# AMC_Connector.net
KiCad netlist of a schematic drawn in Altium Designer
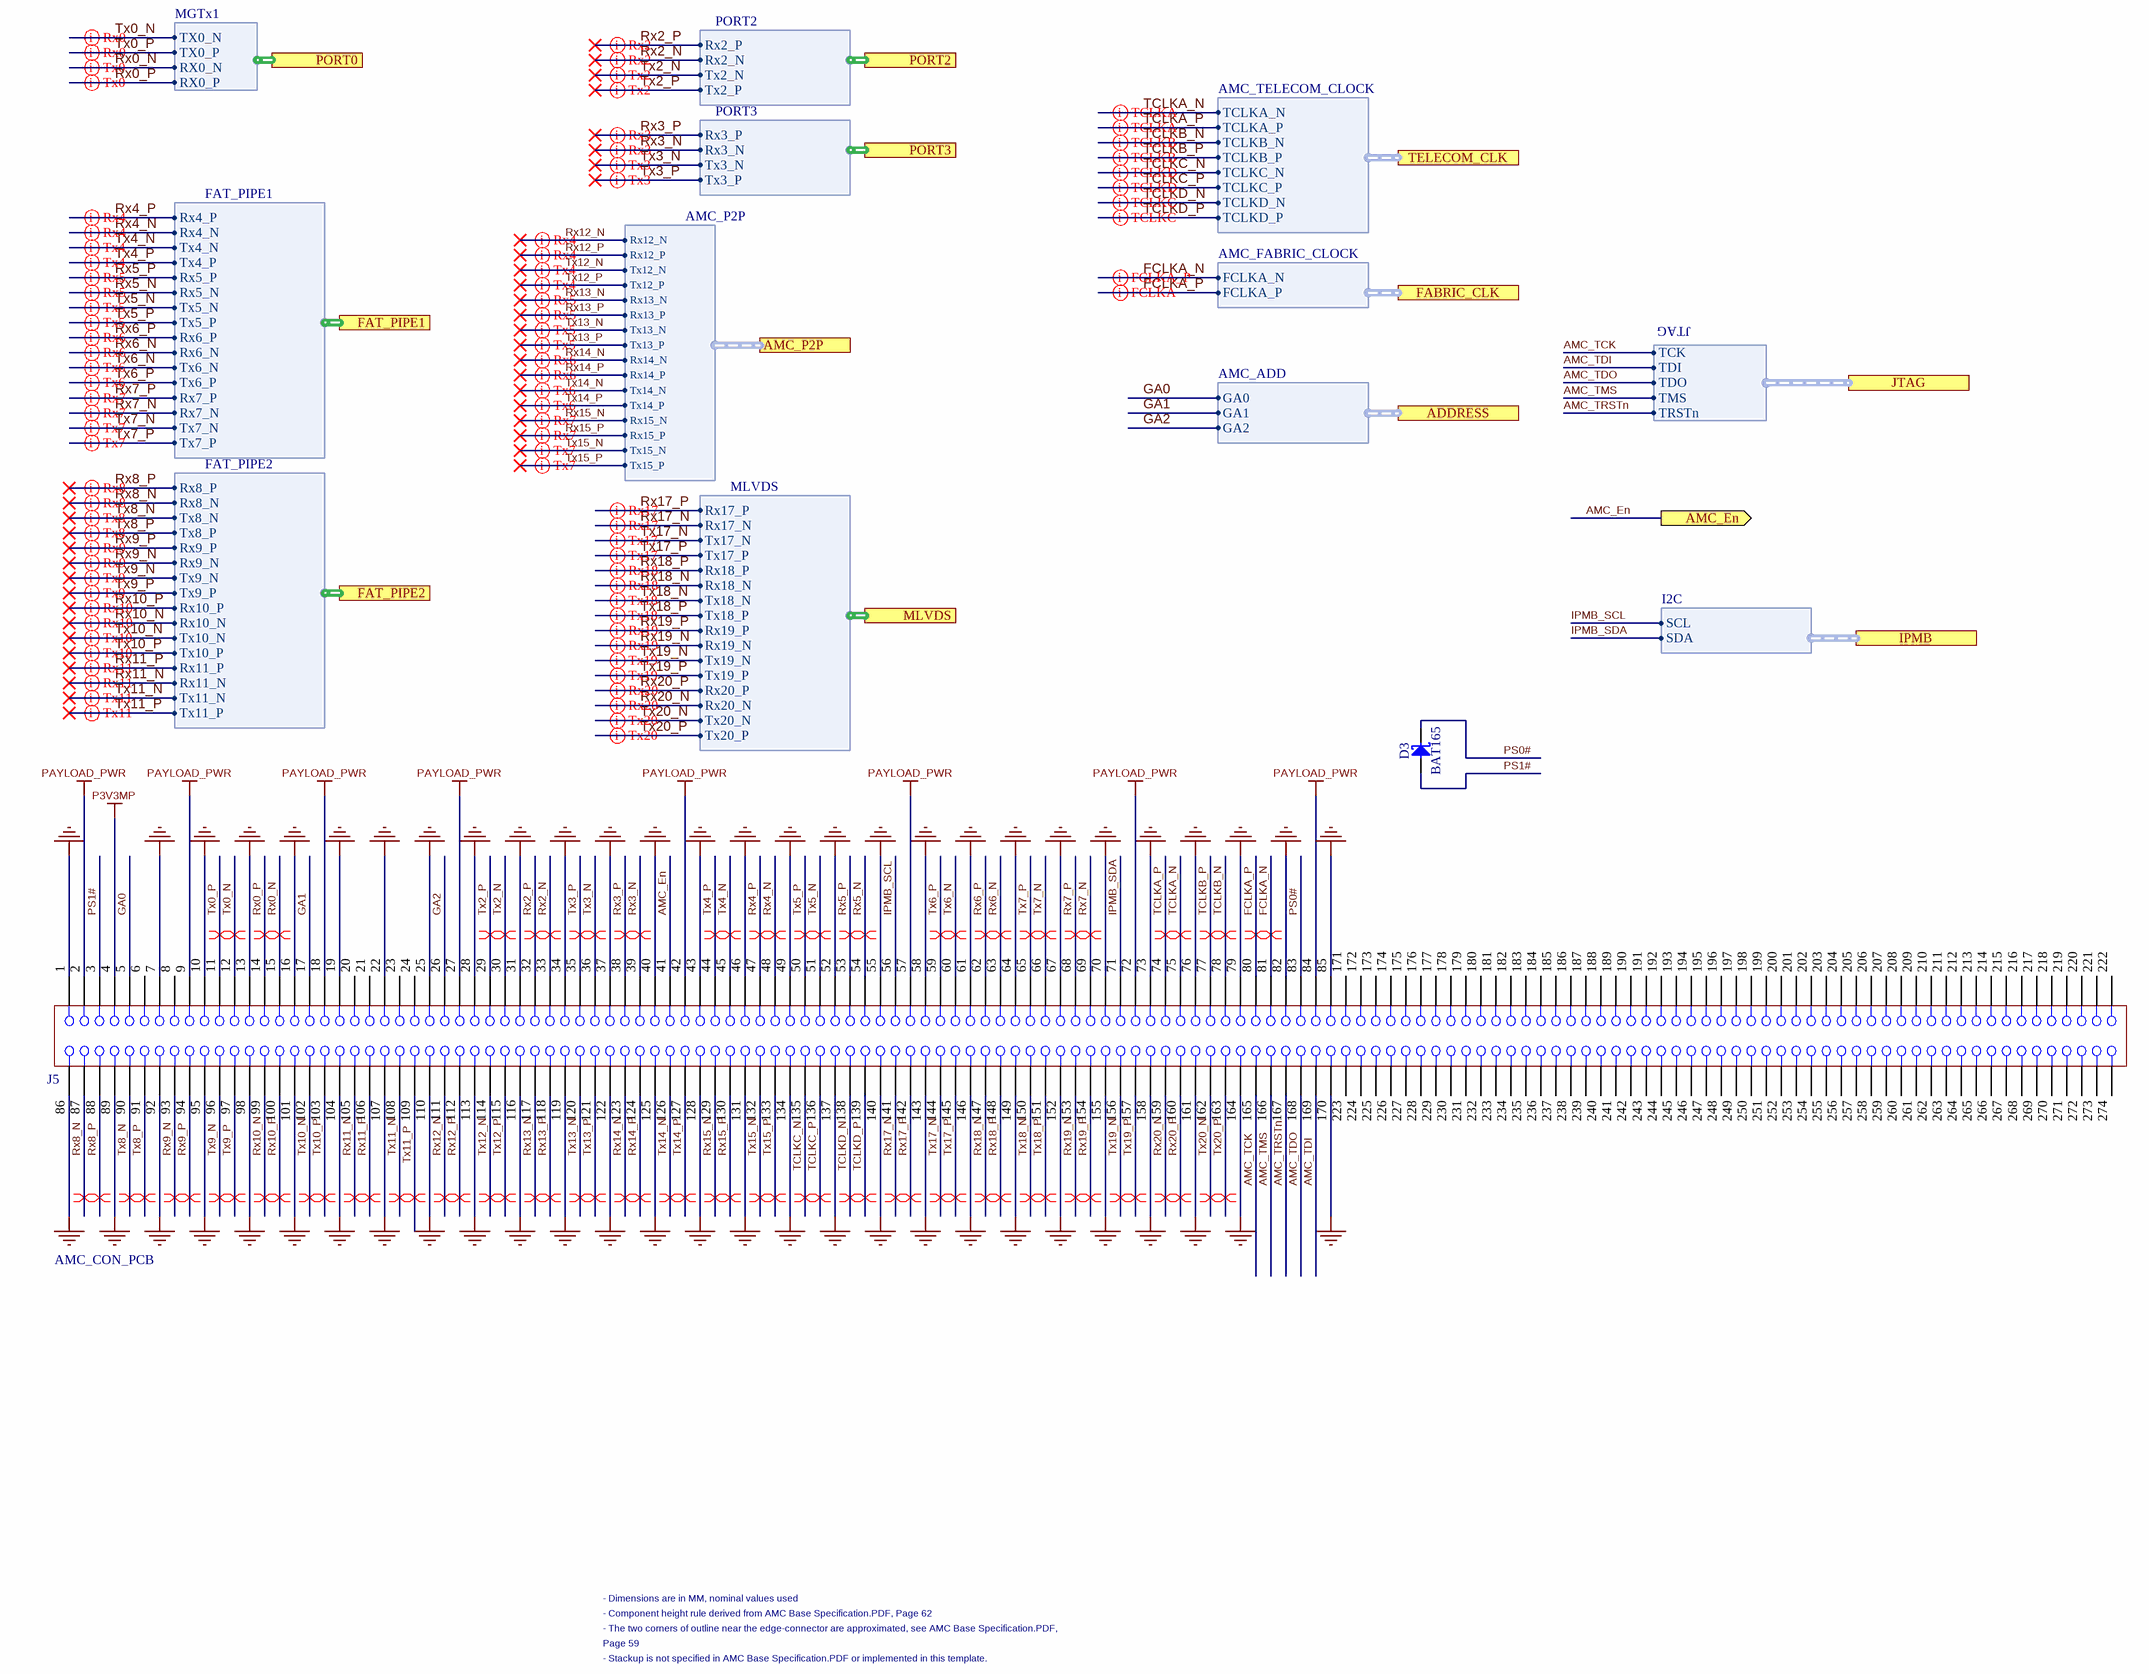
[diagram p0: AMC_Connector.SchDoc]

(export (version "E")
  (design (tool "Eeschema 10.0.6"))
  (components
    (comp (ref "D3")
      (value "BAT165")
      (footprint "SOD2512X110N")
      (description "Schottky Diode")
      (fields
        (field (name "MANUFACTURER") "INFINEON")
        (field (name "VOLTAGE") "40V")
        (field (name "AUTHOR") "CERN DEM JLC")
      )
      (libsource (lib "ICs And Semiconductors") (part "Diode Schottky"))
    )
    (comp (ref "J5")
      (value "AMC_CON_PCB")
      (fields (field (name "MANUFACTURER PART NUMBER") "pcb"))
      (libsource (lib "altium-import") (part "root_0__*"))
    )
  )
  (nets
    (net (code "13") (name "/AMC_En") (class "Default")
      (node (ref "J5") (pin "41") (pinfunction "41_41") (pintype "passive"))
    )
    (net (code "14") (name "/AMC_TCK") (class "Default")
      (node (ref "J5") (pin "165") (pinfunction "165_165") (pintype "passive"))
    )
    (net (code "15") (name "/AMC_TDI") (class "Default")
      (node (ref "J5") (pin "169") (pinfunction "169_169") (pintype "passive"))
    )
    (net (code "16") (name "/AMC_TDO") (class "Default")
      (node (ref "J5") (pin "168") (pinfunction "168_168") (pintype "passive"))
    )
    (net (code "17") (name "/AMC_TMS") (class "Default")
      (node (ref "J5") (pin "166") (pinfunction "166_166") (pintype "passive"))
    )
    (net (code "18") (name "/AMC_TRSTn") (class "Default")
      (node (ref "J5") (pin "167") (pinfunction "167_167") (pintype "passive"))
    )
    (net (code "19") (name "/FCLKA_N") (class "Default")
      (node (ref "J5") (pin "81") (pinfunction "81_81") (pintype "passive"))
    )
    (net (code "20") (name "/FCLKA_P") (class "Default")
      (node (ref "J5") (pin "80") (pinfunction "80_80") (pintype "passive"))
    )
    (net (code "21") (name "/GA0") (class "Default")
      (node (ref "J5") (pin "5") (pinfunction "5_5") (pintype "passive"))
    )
    (net (code "22") (name "/GA1") (class "Default")
      (node (ref "J5") (pin "17") (pinfunction "17_17") (pintype "passive"))
    )
    (net (code "23") (name "/GA2") (class "Default")
      (node (ref "J5") (pin "26") (pinfunction "26_26") (pintype "passive"))
    )
    (net (code "24") (name "/IPMB_SCL") (class "Default")
      (node (ref "J5") (pin "56") (pinfunction "56_56") (pintype "passive"))
    )
    (net (code "25") (name "/IPMB_SDA") (class "Default")
      (node (ref "J5") (pin "71") (pinfunction "71_71") (pintype "passive"))
    )
    (net (code "26") (name "/PS0#") (class "Default")
      (node (ref "D3") (pin "1") (pinfunction "C_1") (pintype "passive"))
      (node (ref "J5") (pin "83") (pinfunction "83_83") (pintype "passive"))
    )
    (net (code "27") (name "/PS1#") (class "Default")
      (node (ref "D3") (pin "2") (pinfunction "A_2") (pintype "passive"))
      (node (ref "J5") (pin "3") (pinfunction "3_3") (pintype "passive"))
    )
    (net (code "28") (name "/Rx0_N") (class "Default")
      (node (ref "J5") (pin "15") (pinfunction "15_15") (pintype "passive"))
    )
    (net (code "29") (name "/Rx0_P") (class "Default")
      (node (ref "J5") (pin "14") (pinfunction "14_14") (pintype "passive"))
    )
    (net (code "30") (name "/Rx2_N") (class "Default")
      (node (ref "J5") (pin "33") (pinfunction "33_33") (pintype "passive"))
    )
    (net (code "31") (name "/Rx2_P") (class "Default")
      (node (ref "J5") (pin "32") (pinfunction "32_32") (pintype "passive"))
    )
    (net (code "32") (name "/Rx3_N") (class "Default")
      (node (ref "J5") (pin "39") (pinfunction "39_39") (pintype "passive"))
    )
    (net (code "33") (name "/Rx3_P") (class "Default")
      (node (ref "J5") (pin "38") (pinfunction "38_38") (pintype "passive"))
    )
    (net (code "34") (name "/Rx4_N") (class "Default")
      (node (ref "J5") (pin "48") (pinfunction "48_48") (pintype "passive"))
    )
    (net (code "35") (name "/Rx4_P") (class "Default")
      (node (ref "J5") (pin "47") (pinfunction "47_47") (pintype "passive"))
    )
    (net (code "36") (name "/Rx5_N") (class "Default")
      (node (ref "J5") (pin "54") (pinfunction "54_54") (pintype "passive"))
    )
    (net (code "37") (name "/Rx5_P") (class "Default")
      (node (ref "J5") (pin "53") (pinfunction "53_53") (pintype "passive"))
    )
    (net (code "38") (name "/Rx6_N") (class "Default")
      (node (ref "J5") (pin "63") (pinfunction "63_63") (pintype "passive"))
    )
    (net (code "39") (name "/Rx6_P") (class "Default")
      (node (ref "J5") (pin "62") (pinfunction "62_62") (pintype "passive"))
    )
    (net (code "40") (name "/Rx7_N") (class "Default")
      (node (ref "J5") (pin "69") (pinfunction "69_69") (pintype "passive"))
    )
    (net (code "41") (name "/Rx7_P") (class "Default")
      (node (ref "J5") (pin "68") (pinfunction "68_68") (pintype "passive"))
    )
    (net (code "42") (name "/Rx8_N") (class "Default")
      (node (ref "J5") (pin "87") (pinfunction "87_87") (pintype "passive"))
    )
    (net (code "43") (name "/Rx8_P") (class "Default")
      (node (ref "J5") (pin "88") (pinfunction "88_88") (pintype "passive"))
    )
    (net (code "44") (name "/Rx9_N") (class "Default")
      (node (ref "J5") (pin "93") (pinfunction "93_93") (pintype "passive"))
    )
    (net (code "45") (name "/Rx9_P") (class "Default")
      (node (ref "J5") (pin "94") (pinfunction "94_94") (pintype "passive"))
    )
    (net (code "46") (name "/Rx10_N") (class "Default")
      (node (ref "J5") (pin "99") (pinfunction "99_99") (pintype "passive"))
    )
    (net (code "47") (name "/Rx10_P") (class "Default")
      (node (ref "J5") (pin "100") (pinfunction "100_100") (pintype "passive"))
    )
    (net (code "48") (name "/Rx11_N") (class "Default")
      (node (ref "J5") (pin "105") (pinfunction "105_105") (pintype "passive"))
    )
    (net (code "49") (name "/Rx11_P") (class "Default")
      (node (ref "J5") (pin "106") (pinfunction "106_106") (pintype "passive"))
    )
    (net (code "50") (name "/Rx12_N") (class "Default")
      (node (ref "J5") (pin "111") (pinfunction "111_111") (pintype "passive"))
    )
    (net (code "51") (name "/Rx12_P") (class "Default")
      (node (ref "J5") (pin "112") (pinfunction "112_112") (pintype "passive"))
    )
    (net (code "52") (name "/Rx13_N") (class "Default")
      (node (ref "J5") (pin "117") (pinfunction "117_117") (pintype "passive"))
    )
    (net (code "53") (name "/Rx13_P") (class "Default")
      (node (ref "J5") (pin "118") (pinfunction "118_118") (pintype "passive"))
    )
    (net (code "54") (name "/Rx14_N") (class "Default")
      (node (ref "J5") (pin "123") (pinfunction "123_123") (pintype "passive"))
    )
    (net (code "55") (name "/Rx14_P") (class "Default")
      (node (ref "J5") (pin "124") (pinfunction "124_124") (pintype "passive"))
    )
    (net (code "56") (name "/Rx15_N") (class "Default")
      (node (ref "J5") (pin "129") (pinfunction "129_129") (pintype "passive"))
    )
    (net (code "57") (name "/Rx15_P") (class "Default")
      (node (ref "J5") (pin "130") (pinfunction "130_130") (pintype "passive"))
    )
    (net (code "58") (name "/Rx17_N") (class "Default")
      (node (ref "J5") (pin "141") (pinfunction "141_141") (pintype "passive"))
    )
    (net (code "59") (name "/Rx17_P") (class "Default")
      (node (ref "J5") (pin "142") (pinfunction "142_142") (pintype "passive"))
    )
    (net (code "60") (name "/Rx18_N") (class "Default")
      (node (ref "J5") (pin "147") (pinfunction "147_147") (pintype "passive"))
    )
    (net (code "61") (name "/Rx18_P") (class "Default")
      (node (ref "J5") (pin "148") (pinfunction "148_148") (pintype "passive"))
    )
    (net (code "62") (name "/Rx19_N") (class "Default")
      (node (ref "J5") (pin "153") (pinfunction "153_153") (pintype "passive"))
    )
    (net (code "63") (name "/Rx19_P") (class "Default")
      (node (ref "J5") (pin "154") (pinfunction "154_154") (pintype "passive"))
    )
    (net (code "64") (name "/Rx20_N") (class "Default")
      (node (ref "J5") (pin "159") (pinfunction "159_159") (pintype "passive"))
    )
    (net (code "65") (name "/Rx20_P") (class "Default")
      (node (ref "J5") (pin "160") (pinfunction "160_160") (pintype "passive"))
    )
    (net (code "66") (name "/TCLKA_N") (class "Default")
      (node (ref "J5") (pin "75") (pinfunction "75_75") (pintype "passive"))
    )
    (net (code "67") (name "/TCLKA_P") (class "Default")
      (node (ref "J5") (pin "74") (pinfunction "74_74") (pintype "passive"))
    )
    (net (code "68") (name "/TCLKB_N") (class "Default")
      (node (ref "J5") (pin "78") (pinfunction "78_78") (pintype "passive"))
    )
    (net (code "69") (name "/TCLKB_P") (class "Default")
      (node (ref "J5") (pin "77") (pinfunction "77_77") (pintype "passive"))
    )
    (net (code "70") (name "/TCLKC_N") (class "Default")
      (node (ref "J5") (pin "135") (pinfunction "135_135") (pintype "passive"))
    )
    (net (code "71") (name "/TCLKC_P") (class "Default")
      (node (ref "J5") (pin "136") (pinfunction "136_136") (pintype "passive"))
    )
    (net (code "72") (name "/TCLKD_N") (class "Default")
      (node (ref "J5") (pin "138") (pinfunction "138_138") (pintype "passive"))
    )
    (net (code "73") (name "/TCLKD_P") (class "Default")
      (node (ref "J5") (pin "139") (pinfunction "139_139") (pintype "passive"))
    )
    (net (code "74") (name "/Tx0_N") (class "Default")
      (node (ref "J5") (pin "12") (pinfunction "12_12") (pintype "passive"))
    )
    (net (code "75") (name "/Tx0_P") (class "Default")
      (node (ref "J5") (pin "11") (pinfunction "11_11") (pintype "passive"))
    )
    (net (code "76") (name "/Tx2_N") (class "Default")
      (node (ref "J5") (pin "30") (pinfunction "30_30") (pintype "passive"))
    )
    (net (code "77") (name "/Tx2_P") (class "Default")
      (node (ref "J5") (pin "29") (pinfunction "29_29") (pintype "passive"))
    )
    (net (code "78") (name "/Tx3_N") (class "Default")
      (node (ref "J5") (pin "36") (pinfunction "36_36") (pintype "passive"))
    )
    (net (code "79") (name "/Tx3_P") (class "Default")
      (node (ref "J5") (pin "35") (pinfunction "35_35") (pintype "passive"))
    )
    (net (code "80") (name "/Tx4_N") (class "Default")
      (node (ref "J5") (pin "45") (pinfunction "45_45") (pintype "passive"))
    )
    (net (code "81") (name "/Tx4_P") (class "Default")
      (node (ref "J5") (pin "44") (pinfunction "44_44") (pintype "passive"))
    )
    (net (code "82") (name "/Tx5_N") (class "Default")
      (node (ref "J5") (pin "51") (pinfunction "51_51") (pintype "passive"))
    )
    (net (code "83") (name "/Tx5_P") (class "Default")
      (node (ref "J5") (pin "50") (pinfunction "50_50") (pintype "passive"))
    )
    (net (code "84") (name "/Tx6_N") (class "Default")
      (node (ref "J5") (pin "60") (pinfunction "60_60") (pintype "passive"))
    )
    (net (code "85") (name "/Tx6_P") (class "Default")
      (node (ref "J5") (pin "59") (pinfunction "59_59") (pintype "passive"))
    )
    (net (code "86") (name "/Tx7_N") (class "Default")
      (node (ref "J5") (pin "66") (pinfunction "66_66") (pintype "passive"))
    )
    (net (code "87") (name "/Tx7_P") (class "Default")
      (node (ref "J5") (pin "65") (pinfunction "65_65") (pintype "passive"))
    )
    (net (code "88") (name "/Tx8_N") (class "Default")
      (node (ref "J5") (pin "90") (pinfunction "90_90") (pintype "passive"))
    )
    (net (code "89") (name "/Tx8_P") (class "Default")
      (node (ref "J5") (pin "91") (pinfunction "91_91") (pintype "passive"))
    )
    (net (code "90") (name "/Tx9_N") (class "Default")
      (node (ref "J5") (pin "96") (pinfunction "96_96") (pintype "passive"))
    )
    (net (code "91") (name "/Tx9_P") (class "Default")
      (node (ref "J5") (pin "97") (pinfunction "97_97") (pintype "passive"))
    )
    (net (code "92") (name "/Tx10_N") (class "Default")
      (node (ref "J5") (pin "102") (pinfunction "102_102") (pintype "passive"))
    )
    (net (code "93") (name "/Tx10_P") (class "Default")
      (node (ref "J5") (pin "103") (pinfunction "103_103") (pintype "passive"))
    )
    (net (code "94") (name "/Tx11_N") (class "Default")
      (node (ref "J5") (pin "108") (pinfunction "108_108") (pintype "passive"))
    )
    (net (code "95") (name "/Tx11_P") (class "Default")
      (node (ref "J5") (pin "109") (pinfunction "109_109") (pintype "passive"))
    )
    (net (code "96") (name "/Tx12_N") (class "Default")
      (node (ref "J5") (pin "114") (pinfunction "114_114") (pintype "passive"))
    )
    (net (code "97") (name "/Tx12_P") (class "Default")
      (node (ref "J5") (pin "115") (pinfunction "115_115") (pintype "passive"))
    )
    (net (code "98") (name "/Tx13_N") (class "Default")
      (node (ref "J5") (pin "120") (pinfunction "120_120") (pintype "passive"))
    )
    (net (code "99") (name "/Tx13_P") (class "Default")
      (node (ref "J5") (pin "121") (pinfunction "121_121") (pintype "passive"))
    )
    (net (code "100") (name "/Tx14_N") (class "Default")
      (node (ref "J5") (pin "126") (pinfunction "126_126") (pintype "passive"))
    )
    (net (code "101") (name "/Tx14_P") (class "Default")
      (node (ref "J5") (pin "127") (pinfunction "127_127") (pintype "passive"))
    )
    (net (code "102") (name "/Tx15_N") (class "Default")
      (node (ref "J5") (pin "132") (pinfunction "132_132") (pintype "passive"))
    )
    (net (code "103") (name "/Tx15_P") (class "Default")
      (node (ref "J5") (pin "133") (pinfunction "133_133") (pintype "passive"))
    )
    (net (code "104") (name "/Tx17_N") (class "Default")
      (node (ref "J5") (pin "144") (pinfunction "144_144") (pintype "passive"))
    )
    (net (code "105") (name "/Tx17_P") (class "Default")
      (node (ref "J5") (pin "145") (pinfunction "145_145") (pintype "passive"))
    )
    (net (code "106") (name "/Tx18_N") (class "Default")
      (node (ref "J5") (pin "150") (pinfunction "150_150") (pintype "passive"))
    )
    (net (code "107") (name "/Tx18_P") (class "Default")
      (node (ref "J5") (pin "151") (pinfunction "151_151") (pintype "passive"))
    )
    (net (code "108") (name "/Tx19_N") (class "Default")
      (node (ref "J5") (pin "156") (pinfunction "156_156") (pintype "passive"))
    )
    (net (code "109") (name "/Tx19_P") (class "Default")
      (node (ref "J5") (pin "157") (pinfunction "157_157") (pintype "passive"))
    )
    (net (code "110") (name "/Tx20_N") (class "Default")
      (node (ref "J5") (pin "162") (pinfunction "162_162") (pintype "passive"))
    )
    (net (code "111") (name "/Tx20_P") (class "Default")
      (node (ref "J5") (pin "163") (pinfunction "163_163") (pintype "passive"))
    )
    (net (code "124") (name "GND") (class "Default")
      (node (ref "J5") (pin "1") (pinfunction "1_1") (pintype "passive"))
      (node (ref "J5") (pin "10") (pinfunction "10_10") (pintype "passive"))
      (node (ref "J5") (pin "101") (pinfunction "101_101") (pintype "passive"))
      (node (ref "J5") (pin "104") (pinfunction "104_104") (pintype "passive"))
      (node (ref "J5") (pin "107") (pinfunction "107_107") (pintype "passive"))
      (node (ref "J5") (pin "110") (pinfunction "110_110") (pintype "passive"))
      (node (ref "J5") (pin "113") (pinfunction "113_113") (pintype "passive"))
      (node (ref "J5") (pin "116") (pinfunction "116_116") (pintype "passive"))
      (node (ref "J5") (pin "119") (pinfunction "119_119") (pintype "passive"))
      (node (ref "J5") (pin "122") (pinfunction "122_122") (pintype "passive"))
      (node (ref "J5") (pin "125") (pinfunction "125_125") (pintype "passive"))
      (node (ref "J5") (pin "128") (pinfunction "128_128") (pintype "passive"))
      (node (ref "J5") (pin "13") (pinfunction "13_13") (pintype "passive"))
      (node (ref "J5") (pin "131") (pinfunction "131_131") (pintype "passive"))
      (node (ref "J5") (pin "134") (pinfunction "134_134") (pintype "passive"))
      (node (ref "J5") (pin "137") (pinfunction "137_137") (pintype "passive"))
      (node (ref "J5") (pin "140") (pinfunction "140_140") (pintype "passive"))
      (node (ref "J5") (pin "143") (pinfunction "143_143") (pintype "passive"))
      (node (ref "J5") (pin "146") (pinfunction "146_146") (pintype "passive"))
      (node (ref "J5") (pin "149") (pinfunction "149_149") (pintype "passive"))
      (node (ref "J5") (pin "152") (pinfunction "152_152") (pintype "passive"))
      (node (ref "J5") (pin "155") (pinfunction "155_155") (pintype "passive"))
      (node (ref "J5") (pin "158") (pinfunction "158_158") (pintype "passive"))
      (node (ref "J5") (pin "16") (pinfunction "16_16") (pintype "passive"))
      (node (ref "J5") (pin "161") (pinfunction "161_161") (pintype "passive"))
      (node (ref "J5") (pin "164") (pinfunction "164_164") (pintype "passive"))
      (node (ref "J5") (pin "170") (pinfunction "170_170") (pintype "passive"))
      (node (ref "J5") (pin "19") (pinfunction "19_19") (pintype "passive"))
      (node (ref "J5") (pin "22") (pinfunction "22_22") (pintype "passive"))
      (node (ref "J5") (pin "25") (pinfunction "25_25") (pintype "passive"))
      (node (ref "J5") (pin "28") (pinfunction "28_28") (pintype "passive"))
      (node (ref "J5") (pin "31") (pinfunction "31_31") (pintype "passive"))
      (node (ref "J5") (pin "34") (pinfunction "34_34") (pintype "passive"))
      (node (ref "J5") (pin "37") (pinfunction "37_37") (pintype "passive"))
      (node (ref "J5") (pin "40") (pinfunction "40_40") (pintype "passive"))
      (node (ref "J5") (pin "43") (pinfunction "43_43") (pintype "passive"))
      (node (ref "J5") (pin "46") (pinfunction "46_46") (pintype "passive"))
      (node (ref "J5") (pin "49") (pinfunction "49_49") (pintype "passive"))
      (node (ref "J5") (pin "52") (pinfunction "52_52") (pintype "passive"))
      (node (ref "J5") (pin "55") (pinfunction "55_55") (pintype "passive"))
      (node (ref "J5") (pin "58") (pinfunction "58_58") (pintype "passive"))
      (node (ref "J5") (pin "61") (pinfunction "61_61") (pintype "passive"))
      (node (ref "J5") (pin "64") (pinfunction "64_64") (pintype "passive"))
      (node (ref "J5") (pin "67") (pinfunction "67_67") (pintype "passive"))
      (node (ref "J5") (pin "7") (pinfunction "7_7") (pintype "passive"))
      (node (ref "J5") (pin "70") (pinfunction "70_70") (pintype "passive"))
      (node (ref "J5") (pin "73") (pinfunction "73_73") (pintype "passive"))
      (node (ref "J5") (pin "76") (pinfunction "76_76") (pintype "passive"))
      (node (ref "J5") (pin "79") (pinfunction "79_79") (pintype "passive"))
      (node (ref "J5") (pin "82") (pinfunction "82_82") (pintype "passive"))
      (node (ref "J5") (pin "85") (pinfunction "85_85") (pintype "passive"))
      (node (ref "J5") (pin "86") (pinfunction "86_86") (pintype "passive"))
      (node (ref "J5") (pin "89") (pinfunction "89_89") (pintype "passive"))
      (node (ref "J5") (pin "92") (pinfunction "92_92") (pintype "passive"))
      (node (ref "J5") (pin "95") (pinfunction "95_95") (pintype "passive"))
      (node (ref "J5") (pin "98") (pinfunction "98_98") (pintype "passive"))
    )
    (net (code "125") (name "P3V3MP") (class "Default")
      (node (ref "J5") (pin "4") (pinfunction "4_4") (pintype "passive"))
    )
    (net (code "126") (name "PAYLOAD_PWR") (class "Default")
      (node (ref "J5") (pin "18") (pinfunction "18_18") (pintype "passive"))
      (node (ref "J5") (pin "2") (pinfunction "2_2") (pintype "passive"))
      (node (ref "J5") (pin "27") (pinfunction "27_27") (pintype "passive"))
      (node (ref "J5") (pin "42") (pinfunction "42_42") (pintype "passive"))
      (node (ref "J5") (pin "57") (pinfunction "57_57") (pintype "passive"))
      (node (ref "J5") (pin "72") (pinfunction "72_72") (pintype "passive"))
      (node (ref "J5") (pin "84") (pinfunction "84_84") (pintype "passive"))
      (node (ref "J5") (pin "9") (pinfunction "9_9") (pintype "passive"))
    )
    (net (code "127") (name "unconnected-(J5-Pad6)") (class "Default")
      (node (ref "J5") (pin "6") (pinfunction "6_6") (pintype "passive"))
    )
    (net (code "128") (name "unconnected-(J5-Pad8)") (class "Default")
      (node (ref "J5") (pin "8") (pinfunction "8_8") (pintype "passive"))
    )
    (net (code "129") (name "unconnected-(J5-Pad20)") (class "Default")
      (node (ref "J5") (pin "20") (pinfunction "20_20") (pintype "passive"))
    )
    (net (code "130") (name "unconnected-(J5-Pad21)") (class "Default")
      (node (ref "J5") (pin "21") (pinfunction "21_21") (pintype "passive"))
    )
    (net (code "131") (name "unconnected-(J5-Pad23)") (class "Default")
      (node (ref "J5") (pin "23") (pinfunction "23_23") (pintype "passive"))
    )
    (net (code "132") (name "unconnected-(J5-Pad24)") (class "Default")
      (node (ref "J5") (pin "24") (pinfunction "24_24") (pintype "passive"))
    )
    (net (code "133") (name "unconnected-(J5-Pad171)") (class "Default")
      (node (ref "J5") (pin "171") (pinfunction "171_171") (pintype "passive"))
    )
    (net (code "134") (name "unconnected-(J5-Pad172)") (class "Default")
      (node (ref "J5") (pin "172") (pinfunction "172_172") (pintype "passive"))
    )
    (net (code "135") (name "unconnected-(J5-Pad173)") (class "Default")
      (node (ref "J5") (pin "173") (pinfunction "173_173") (pintype "passive"))
    )
    (net (code "136") (name "unconnected-(J5-Pad174)") (class "Default")
      (node (ref "J5") (pin "174") (pinfunction "174_174") (pintype "passive"))
    )
    (net (code "137") (name "unconnected-(J5-Pad175)") (class "Default")
      (node (ref "J5") (pin "175") (pinfunction "175_175") (pintype "passive"))
    )
    (net (code "138") (name "unconnected-(J5-Pad176)") (class "Default")
      (node (ref "J5") (pin "176") (pinfunction "176_176") (pintype "passive"))
    )
    (net (code "139") (name "unconnected-(J5-Pad177)") (class "Default")
      (node (ref "J5") (pin "177") (pinfunction "177_177") (pintype "passive"))
    )
    (net (code "140") (name "unconnected-(J5-Pad178)") (class "Default")
      (node (ref "J5") (pin "178") (pinfunction "178_178") (pintype "passive"))
    )
    (net (code "141") (name "unconnected-(J5-Pad179)") (class "Default")
      (node (ref "J5") (pin "179") (pinfunction "179_179") (pintype "passive"))
    )
    (net (code "142") (name "unconnected-(J5-Pad180)") (class "Default")
      (node (ref "J5") (pin "180") (pinfunction "180_180") (pintype "passive"))
    )
    (net (code "143") (name "unconnected-(J5-Pad181)") (class "Default")
      (node (ref "J5") (pin "181") (pinfunction "181_181") (pintype "passive"))
    )
    (net (code "144") (name "unconnected-(J5-Pad182)") (class "Default")
      (node (ref "J5") (pin "182") (pinfunction "182_182") (pintype "passive"))
    )
    (net (code "145") (name "unconnected-(J5-Pad183)") (class "Default")
      (node (ref "J5") (pin "183") (pinfunction "183_183") (pintype "passive"))
    )
    (net (code "146") (name "unconnected-(J5-Pad184)") (class "Default")
      (node (ref "J5") (pin "184") (pinfunction "184_184") (pintype "passive"))
    )
    (net (code "147") (name "unconnected-(J5-Pad185)") (class "Default")
      (node (ref "J5") (pin "185") (pinfunction "185_185") (pintype "passive"))
    )
    (net (code "148") (name "unconnected-(J5-Pad186)") (class "Default")
      (node (ref "J5") (pin "186") (pinfunction "186_186") (pintype "passive"))
    )
    (net (code "149") (name "unconnected-(J5-Pad187)") (class "Default")
      (node (ref "J5") (pin "187") (pinfunction "187_187") (pintype "passive"))
    )
    (net (code "150") (name "unconnected-(J5-Pad188)") (class "Default")
      (node (ref "J5") (pin "188") (pinfunction "188_188") (pintype "passive"))
    )
    (net (code "151") (name "unconnected-(J5-Pad189)") (class "Default")
      (node (ref "J5") (pin "189") (pinfunction "189_189") (pintype "passive"))
    )
    (net (code "152") (name "unconnected-(J5-Pad190)") (class "Default")
      (node (ref "J5") (pin "190") (pinfunction "190_190") (pintype "passive"))
    )
    (net (code "153") (name "unconnected-(J5-Pad191)") (class "Default")
      (node (ref "J5") (pin "191") (pinfunction "191_191") (pintype "passive"))
    )
    (net (code "154") (name "unconnected-(J5-Pad192)") (class "Default")
      (node (ref "J5") (pin "192") (pinfunction "192_192") (pintype "passive"))
    )
    (net (code "155") (name "unconnected-(J5-Pad193)") (class "Default")
      (node (ref "J5") (pin "193") (pinfunction "193_193") (pintype "passive"))
    )
    (net (code "156") (name "unconnected-(J5-Pad194)") (class "Default")
      (node (ref "J5") (pin "194") (pinfunction "194_194") (pintype "passive"))
    )
    (net (code "157") (name "unconnected-(J5-Pad195)") (class "Default")
      (node (ref "J5") (pin "195") (pinfunction "195_195") (pintype "passive"))
    )
    (net (code "158") (name "unconnected-(J5-Pad196)") (class "Default")
      (node (ref "J5") (pin "196") (pinfunction "196_196") (pintype "passive"))
    )
    (net (code "159") (name "unconnected-(J5-Pad197)") (class "Default")
      (node (ref "J5") (pin "197") (pinfunction "197_197") (pintype "passive"))
    )
    (net (code "160") (name "unconnected-(J5-Pad198)") (class "Default")
      (node (ref "J5") (pin "198") (pinfunction "198_198") (pintype "passive"))
    )
    (net (code "161") (name "unconnected-(J5-Pad199)") (class "Default")
      (node (ref "J5") (pin "199") (pinfunction "199_199") (pintype "passive"))
    )
    (net (code "162") (name "unconnected-(J5-Pad200)") (class "Default")
      (node (ref "J5") (pin "200") (pinfunction "200_200") (pintype "passive"))
    )
    (net (code "163") (name "unconnected-(J5-Pad201)") (class "Default")
      (node (ref "J5") (pin "201") (pinfunction "201_201") (pintype "passive"))
    )
    (net (code "164") (name "unconnected-(J5-Pad202)") (class "Default")
      (node (ref "J5") (pin "202") (pinfunction "202_202") (pintype "passive"))
    )
    (net (code "165") (name "unconnected-(J5-Pad203)") (class "Default")
      (node (ref "J5") (pin "203") (pinfunction "203_203") (pintype "passive"))
    )
    (net (code "166") (name "unconnected-(J5-Pad204)") (class "Default")
      (node (ref "J5") (pin "204") (pinfunction "204_204") (pintype "passive"))
    )
    (net (code "167") (name "unconnected-(J5-Pad205)") (class "Default")
      (node (ref "J5") (pin "205") (pinfunction "205_205") (pintype "passive"))
    )
    (net (code "168") (name "unconnected-(J5-Pad206)") (class "Default")
      (node (ref "J5") (pin "206") (pinfunction "206_206") (pintype "passive"))
    )
    (net (code "169") (name "unconnected-(J5-Pad207)") (class "Default")
      (node (ref "J5") (pin "207") (pinfunction "207_207") (pintype "passive"))
    )
    (net (code "170") (name "unconnected-(J5-Pad208)") (class "Default")
      (node (ref "J5") (pin "208") (pinfunction "208_208") (pintype "passive"))
    )
    (net (code "171") (name "unconnected-(J5-Pad209)") (class "Default")
      (node (ref "J5") (pin "209") (pinfunction "209_209") (pintype "passive"))
    )
    (net (code "172") (name "unconnected-(J5-Pad210)") (class "Default")
      (node (ref "J5") (pin "210") (pinfunction "210_210") (pintype "passive"))
    )
    (net (code "173") (name "unconnected-(J5-Pad211)") (class "Default")
      (node (ref "J5") (pin "211") (pinfunction "211_211") (pintype "passive"))
    )
    (net (code "174") (name "unconnected-(J5-Pad212)") (class "Default")
      (node (ref "J5") (pin "212") (pinfunction "212_212") (pintype "passive"))
    )
    (net (code "175") (name "unconnected-(J5-Pad213)") (class "Default")
      (node (ref "J5") (pin "213") (pinfunction "213_213") (pintype "passive"))
    )
    (net (code "176") (name "unconnected-(J5-Pad214)") (class "Default")
      (node (ref "J5") (pin "214") (pinfunction "214_214") (pintype "passive"))
    )
    (net (code "177") (name "unconnected-(J5-Pad215)") (class "Default")
      (node (ref "J5") (pin "215") (pinfunction "215_215") (pintype "passive"))
    )
    (net (code "178") (name "unconnected-(J5-Pad216)") (class "Default")
      (node (ref "J5") (pin "216") (pinfunction "216_216") (pintype "passive"))
    )
    (net (code "179") (name "unconnected-(J5-Pad217)") (class "Default")
      (node (ref "J5") (pin "217") (pinfunction "217_217") (pintype "passive"))
    )
    (net (code "180") (name "unconnected-(J5-Pad218)") (class "Default")
      (node (ref "J5") (pin "218") (pinfunction "218_218") (pintype "passive"))
    )
    (net (code "181") (name "unconnected-(J5-Pad219)") (class "Default")
      (node (ref "J5") (pin "219") (pinfunction "219_219") (pintype "passive"))
    )
    (net (code "182") (name "unconnected-(J5-Pad220)") (class "Default")
      (node (ref "J5") (pin "220") (pinfunction "220_220") (pintype "passive"))
    )
    (net (code "183") (name "unconnected-(J5-Pad221)") (class "Default")
      (node (ref "J5") (pin "221") (pinfunction "221_221") (pintype "passive"))
    )
    (net (code "184") (name "unconnected-(J5-Pad222)") (class "Default")
      (node (ref "J5") (pin "222") (pinfunction "222_222") (pintype "passive"))
    )
    (net (code "185") (name "unconnected-(J5-Pad223)") (class "Default")
      (node (ref "J5") (pin "223") (pinfunction "223_223") (pintype "passive"))
    )
    (net (code "186") (name "unconnected-(J5-Pad224)") (class "Default")
      (node (ref "J5") (pin "224") (pinfunction "224_224") (pintype "passive"))
    )
    (net (code "187") (name "unconnected-(J5-Pad225)") (class "Default")
      (node (ref "J5") (pin "225") (pinfunction "225_225") (pintype "passive"))
    )
    (net (code "188") (name "unconnected-(J5-Pad226)") (class "Default")
      (node (ref "J5") (pin "226") (pinfunction "226_226") (pintype "passive"))
    )
    (net (code "189") (name "unconnected-(J5-Pad227)") (class "Default")
      (node (ref "J5") (pin "227") (pinfunction "227_227") (pintype "passive"))
    )
    (net (code "190") (name "unconnected-(J5-Pad228)") (class "Default")
      (node (ref "J5") (pin "228") (pinfunction "228_228") (pintype "passive"))
    )
    (net (code "191") (name "unconnected-(J5-Pad229)") (class "Default")
      (node (ref "J5") (pin "229") (pinfunction "229_229") (pintype "passive"))
    )
    (net (code "192") (name "unconnected-(J5-Pad230)") (class "Default")
      (node (ref "J5") (pin "230") (pinfunction "230_230") (pintype "passive"))
    )
    (net (code "193") (name "unconnected-(J5-Pad231)") (class "Default")
      (node (ref "J5") (pin "231") (pinfunction "231_231") (pintype "passive"))
    )
    (net (code "194") (name "unconnected-(J5-Pad232)") (class "Default")
      (node (ref "J5") (pin "232") (pinfunction "232_232") (pintype "passive"))
    )
    (net (code "195") (name "unconnected-(J5-Pad233)") (class "Default")
      (node (ref "J5") (pin "233") (pinfunction "233_233") (pintype "passive"))
    )
    (net (code "196") (name "unconnected-(J5-Pad234)") (class "Default")
      (node (ref "J5") (pin "234") (pinfunction "234_234") (pintype "passive"))
    )
    (net (code "197") (name "unconnected-(J5-Pad235)") (class "Default")
      (node (ref "J5") (pin "235") (pinfunction "235_235") (pintype "passive"))
    )
    (net (code "198") (name "unconnected-(J5-Pad236)") (class "Default")
      (node (ref "J5") (pin "236") (pinfunction "236_236") (pintype "passive"))
    )
    (net (code "199") (name "unconnected-(J5-Pad237)") (class "Default")
      (node (ref "J5") (pin "237") (pinfunction "237_237") (pintype "passive"))
    )
    (net (code "200") (name "unconnected-(J5-Pad238)") (class "Default")
      (node (ref "J5") (pin "238") (pinfunction "238_238") (pintype "passive"))
    )
    (net (code "201") (name "unconnected-(J5-Pad239)") (class "Default")
      (node (ref "J5") (pin "239") (pinfunction "239_239") (pintype "passive"))
    )
    (net (code "202") (name "unconnected-(J5-Pad240)") (class "Default")
      (node (ref "J5") (pin "240") (pinfunction "240_240") (pintype "passive"))
    )
    (net (code "203") (name "unconnected-(J5-Pad241)") (class "Default")
      (node (ref "J5") (pin "241") (pinfunction "241_241") (pintype "passive"))
    )
    (net (code "204") (name "unconnected-(J5-Pad242)") (class "Default")
      (node (ref "J5") (pin "242") (pinfunction "242_242") (pintype "passive"))
    )
    (net (code "205") (name "unconnected-(J5-Pad243)") (class "Default")
      (node (ref "J5") (pin "243") (pinfunction "243_243") (pintype "passive"))
    )
    (net (code "206") (name "unconnected-(J5-Pad244)") (class "Default")
      (node (ref "J5") (pin "244") (pinfunction "244_244") (pintype "passive"))
    )
    (net (code "207") (name "unconnected-(J5-Pad245)") (class "Default")
      (node (ref "J5") (pin "245") (pinfunction "245_245") (pintype "passive"))
    )
    (net (code "208") (name "unconnected-(J5-Pad246)") (class "Default")
      (node (ref "J5") (pin "246") (pinfunction "246_246") (pintype "passive"))
    )
    (net (code "209") (name "unconnected-(J5-Pad247)") (class "Default")
      (node (ref "J5") (pin "247") (pinfunction "247_247") (pintype "passive"))
    )
    (net (code "210") (name "unconnected-(J5-Pad248)") (class "Default")
      (node (ref "J5") (pin "248") (pinfunction "248_248") (pintype "passive"))
    )
    (net (code "211") (name "unconnected-(J5-Pad249)") (class "Default")
      (node (ref "J5") (pin "249") (pinfunction "249_249") (pintype "passive"))
    )
    (net (code "212") (name "unconnected-(J5-Pad250)") (class "Default")
      (node (ref "J5") (pin "250") (pinfunction "250_250") (pintype "passive"))
    )
    (net (code "213") (name "unconnected-(J5-Pad251)") (class "Default")
      (node (ref "J5") (pin "251") (pinfunction "251_251") (pintype "passive"))
    )
    (net (code "214") (name "unconnected-(J5-Pad252)") (class "Default")
      (node (ref "J5") (pin "252") (pinfunction "252_252") (pintype "passive"))
    )
    (net (code "215") (name "unconnected-(J5-Pad253)") (class "Default")
      (node (ref "J5") (pin "253") (pinfunction "253_253") (pintype "passive"))
    )
    (net (code "216") (name "unconnected-(J5-Pad254)") (class "Default")
      (node (ref "J5") (pin "254") (pinfunction "254_254") (pintype "passive"))
    )
    (net (code "217") (name "unconnected-(J5-Pad255)") (class "Default")
      (node (ref "J5") (pin "255") (pinfunction "255_255") (pintype "passive"))
    )
    (net (code "218") (name "unconnected-(J5-Pad256)") (class "Default")
      (node (ref "J5") (pin "256") (pinfunction "256_256") (pintype "passive"))
    )
    (net (code "219") (name "unconnected-(J5-Pad257)") (class "Default")
      (node (ref "J5") (pin "257") (pinfunction "257_257") (pintype "passive"))
    )
    (net (code "220") (name "unconnected-(J5-Pad258)") (class "Default")
      (node (ref "J5") (pin "258") (pinfunction "258_258") (pintype "passive"))
    )
    (net (code "221") (name "unconnected-(J5-Pad259)") (class "Default")
      (node (ref "J5") (pin "259") (pinfunction "259_259") (pintype "passive"))
    )
    (net (code "222") (name "unconnected-(J5-Pad260)") (class "Default")
      (node (ref "J5") (pin "260") (pinfunction "260_260") (pintype "passive"))
    )
    (net (code "223") (name "unconnected-(J5-Pad261)") (class "Default")
      (node (ref "J5") (pin "261") (pinfunction "261_261") (pintype "passive"))
    )
    (net (code "224") (name "unconnected-(J5-Pad262)") (class "Default")
      (node (ref "J5") (pin "262") (pinfunction "262_262") (pintype "passive"))
    )
    (net (code "225") (name "unconnected-(J5-Pad263)") (class "Default")
      (node (ref "J5") (pin "263") (pinfunction "263_263") (pintype "passive"))
    )
    (net (code "226") (name "unconnected-(J5-Pad264)") (class "Default")
      (node (ref "J5") (pin "264") (pinfunction "264_264") (pintype "passive"))
    )
    (net (code "227") (name "unconnected-(J5-Pad265)") (class "Default")
      (node (ref "J5") (pin "265") (pinfunction "265_265") (pintype "passive"))
    )
    (net (code "228") (name "unconnected-(J5-Pad266)") (class "Default")
      (node (ref "J5") (pin "266") (pinfunction "266_266") (pintype "passive"))
    )
    (net (code "229") (name "unconnected-(J5-Pad267)") (class "Default")
      (node (ref "J5") (pin "267") (pinfunction "267_267") (pintype "passive"))
    )
    (net (code "230") (name "unconnected-(J5-Pad268)") (class "Default")
      (node (ref "J5") (pin "268") (pinfunction "268_268") (pintype "passive"))
    )
    (net (code "231") (name "unconnected-(J5-Pad269)") (class "Default")
      (node (ref "J5") (pin "269") (pinfunction "269_269") (pintype "passive"))
    )
    (net (code "232") (name "unconnected-(J5-Pad270)") (class "Default")
      (node (ref "J5") (pin "270") (pinfunction "270_270") (pintype "passive"))
    )
    (net (code "233") (name "unconnected-(J5-Pad271)") (class "Default")
      (node (ref "J5") (pin "271") (pinfunction "271_271") (pintype "passive"))
    )
    (net (code "234") (name "unconnected-(J5-Pad272)") (class "Default")
      (node (ref "J5") (pin "272") (pinfunction "272_272") (pintype "passive"))
    )
    (net (code "235") (name "unconnected-(J5-Pad273)") (class "Default")
      (node (ref "J5") (pin "273") (pinfunction "273_273") (pintype "passive"))
    )
    (net (code "236") (name "unconnected-(J5-Pad274)") (class "Default")
      (node (ref "J5") (pin "274") (pinfunction "274_274") (pintype "passive"))
    )
  )
)
